# MOTOR.net
KiCad netlist of a schematic drawn in Altium Designer
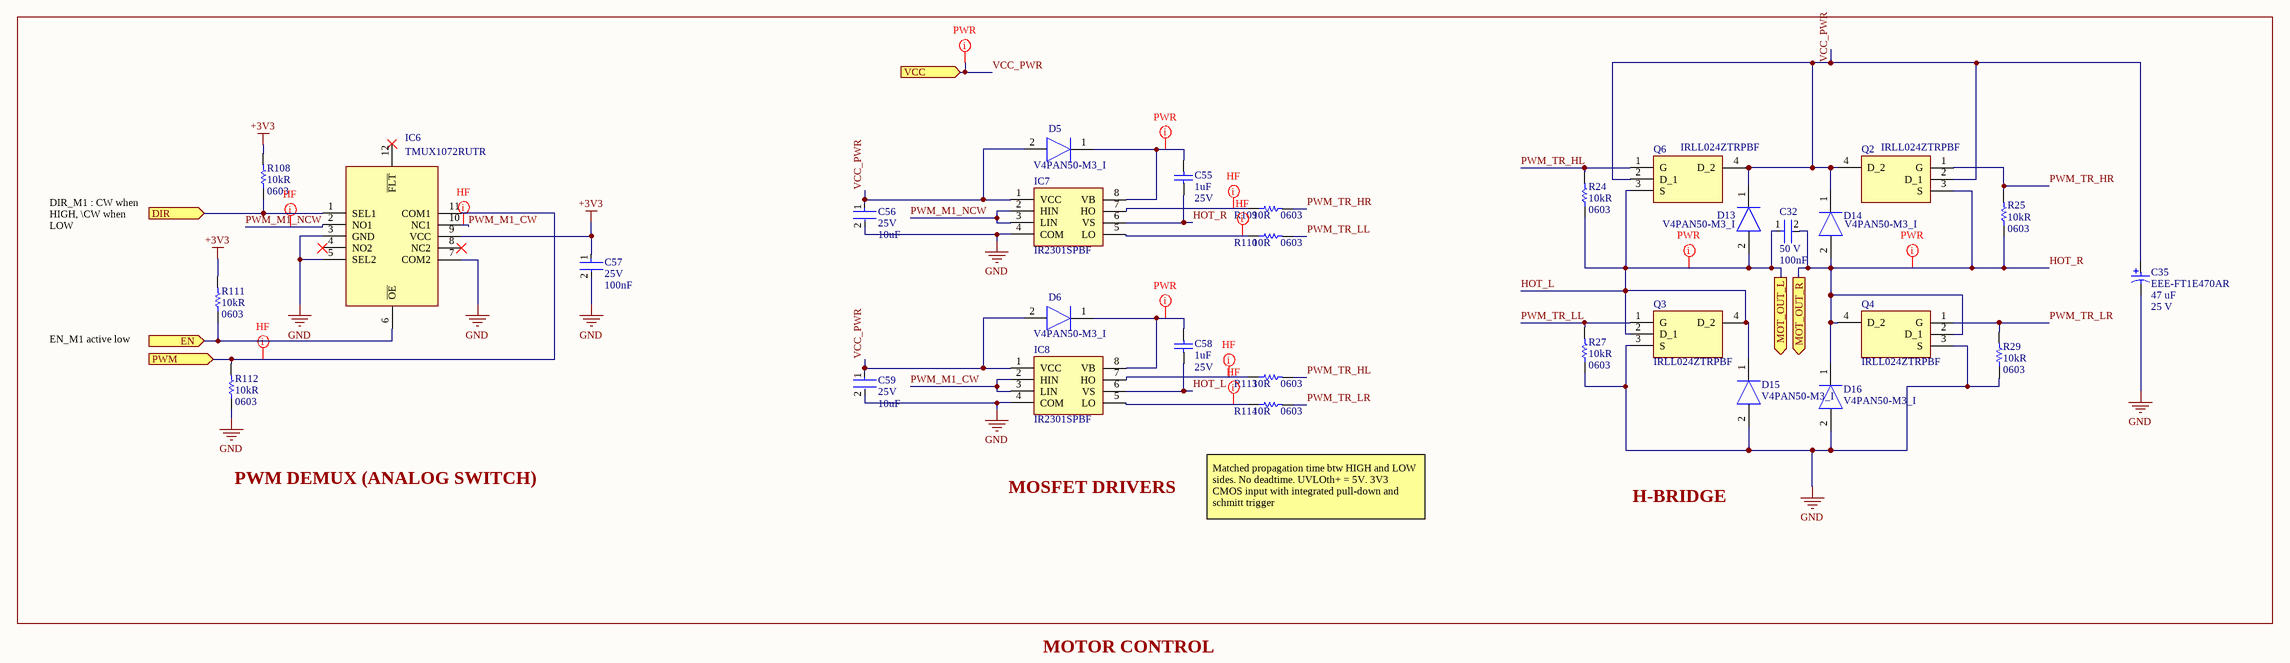
[diagram p0: MOTOR.SchDoc]

(export (version "E")
  (design (tool "Eeschema 10.0.6"))
  (components
    (comp (ref "C32")
      (value "100nF")
      (footprint "FP-C0805C-DN-MFG")
      (description "CAP CER 0.1UF 50V X7R 0805")
      (fields
        (field (name "MANUFACTURER PART NUMBER") "C0805C104K5RACTU")
        (field (name "VOLTAGE RATING") "50 V")
        (field (name "MANUFACTURER") "KEMET")
      )
      (libsource (lib "Altium Content Vault") (part "b4654b650e69147ec39a6b967a45e02"))
    )
    (comp (ref "C35")
      (value "EEE-FT1E470AR")
      (footprint "PNSC-FT-V-53x53-2_V")
      (fields
        (field (name "CAP.") "47 uF")
        (field (name "MANUFACTURER") "Panasonic")
        (field (name "RATED VOLTAGE") "25 V")
      )
      (libsource (lib "Altium Content Vault") (part "PNSC-CAP-P-2"))
    )
    (comp (ref "C55")
      (value "C0603C105K3PAC7867")
      (footprint "CAPC1608X90X35LL15T15")
      (fields
        (field (name "MANUFACTURER") "Kemet")
        (field (name "MANUFACTURER PART NUMBER") "C0603C105K3PACTU")
        (field (name "CAPACITANCE") "1uF")
        (field (name "TOLERANCE") "10%")
        (field (name "VOLTAGE RATING (DC)") "25V")
      )
      (libsource (lib "Altium Content Vault") (part "CAP"))
    )
    (comp (ref "C56")
      (value "C2012X5R1E106K125AB")
      (footprint "FP-C2012-125-0_2-IPC_B")
      (description "Multilayer Ceramic Capacitors 10μF ±10% 25V X5R SMD 0805")
      (fields
        (field (name "VOLTAGE") "25V")
        (field (name "VOLTAGE RATING (DC)") "25V")
        (field (name "TOLERANCE") "10%")
        (field (name "CAPACITANCE") "10uF")
      )
      (libsource (lib "Altium Content Vault") (part "b4654b650e69147ec39a6b967a45e02"))
    )
    (comp (ref "C57")
      (value "CGA3E2X7R1E104K080AA")
      (footprint "FP-CGA3E-0_3-0_1-MFG")
      (description "Cap Ceramic 100nF 25V X7R 10% Pad SMD 0603 +125°C Automotive T/R")
      (fields
        (field (name "VOLTAGE RATING (DC)") "25V")
        (field (name "CAPACITANCE") "100nF")
        (field (name "TOLERANCE") "10%")
        (field (name "MANUFACTURER") "TDK")
      )
      (libsource (lib "Altium Content Vault") (part "b4654b650e69147ec39a6b967a45e02"))
    )
    (comp (ref "C58")
      (value "C0603C105K3PAC7867")
      (footprint "CAPC1608X90X35LL15T15")
      (fields
        (field (name "MANUFACTURER") "Kemet")
        (field (name "MANUFACTURER PART NUMBER") "C0603C105K3PACTU")
        (field (name "CAPACITANCE") "1uF")
        (field (name "TOLERANCE") "10%")
        (field (name "VOLTAGE RATING (DC)") "25V")
      )
      (libsource (lib "Altium Content Vault") (part "CAP"))
    )
    (comp (ref "C59")
      (value "C2012X5R1E106K125AB")
      (footprint "FP-C2012-125-0_2-IPC_B")
      (description "Multilayer Ceramic Capacitors 10μF ±10% 25V X5R SMD 0805")
      (fields
        (field (name "VOLTAGE") "25V")
        (field (name "VOLTAGE RATING (DC)") "25V")
        (field (name "TOLERANCE") "10%")
        (field (name "CAPACITANCE") "10uF")
      )
      (libsource (lib "Altium Content Vault") (part "b4654b650e69147ec39a6b967a45e02"))
    )
    (comp (ref "D5")
      (value "V4PAN50-M3_I")
      (footprint "SamacSys:V4PAN50M3I")
      (description "Diode")
      (fields
        (field (name "MANUFACTURER_PART_NUMBER") "V4PAN50-M3/I")
        (field (name "MOUSER PART NUMBER") "78-V4PAN50-M3/I")
      )
      (libsource (lib "*") (part "V4PAN50-M3_I"))
    )
    (comp (ref "D6")
      (value "V4PAN50-M3_I")
      (footprint "SamacSys:V4PAN50M3I")
      (description "Diode")
      (fields
        (field (name "MANUFACTURER_PART_NUMBER") "V4PAN50-M3/I")
        (field (name "MOUSER PART NUMBER") "78-V4PAN50-M3/I")
      )
      (libsource (lib "*") (part "V4PAN50-M3_I"))
    )
    (comp (ref "D13")
      (value "V4PAN50-M3_I")
      (footprint "SamacSys:V4PAN50M3I")
      (description "Diode")
      (fields
        (field (name "MANUFACTURER_PART_NUMBER") "V4PAN50-M3/I")
        (field (name "MOUSER PART NUMBER") "78-V4PAN50-M3/I")
      )
      (libsource (lib "*") (part "V4PAN50-M3_I"))
    )
    (comp (ref "D14")
      (value "V4PAN50-M3_I")
      (footprint "SamacSys:V4PAN50M3I")
      (description "Diode")
      (fields
        (field (name "MANUFACTURER_PART_NUMBER") "V4PAN50-M3/I")
        (field (name "MOUSER PART NUMBER") "78-V4PAN50-M3/I")
      )
      (libsource (lib "*") (part "V4PAN50-M3_I"))
    )
    (comp (ref "D15")
      (value "V4PAN50-M3_I")
      (footprint "SamacSys:V4PAN50M3I")
      (description "Diode")
      (fields
        (field (name "MANUFACTURER_PART_NUMBER") "V4PAN50-M3/I")
        (field (name "MOUSER PART NUMBER") "78-V4PAN50-M3/I")
      )
      (libsource (lib "*") (part "V4PAN50-M3_I"))
    )
    (comp (ref "D16")
      (value "V4PAN50-M3_I")
      (footprint "SamacSys:V4PAN50M3I")
      (description "Diode")
      (fields
        (field (name "MANUFACTURER_PART_NUMBER") "V4PAN50-M3/I")
        (field (name "MOUSER PART NUMBER") "78-V4PAN50-M3/I")
      )
      (libsource (lib "*") (part "V4PAN50-M3_I"))
    )
    (comp (ref "IC6")
      (value "TMUX1072RUTR")
      (footprint "SamacSys:QFN40P170X200X55-12N")
      (description "Integrated Circuit")
      (fields (field (name "MOUSER PART NUMBER") "595-TMUX1072RUTR"))
      (libsource (lib "*") (part "TMUX1072RUTR"))
    )
    (comp (ref "IC7")
      (value "IR2301SPBF")
      (footprint "SamacSys:SOIC127P600X175-8N")
      (description "Integrated Circuit")
      (fields (field (name "MOUSER PART NUMBER") "942-IR2301SPBF"))
      (libsource (lib "*") (part "IR2301SPBF"))
    )
    (comp (ref "IC8")
      (value "IR2301SPBF")
      (footprint "SamacSys:SOIC127P600X175-8N")
      (description "Integrated Circuit")
      (fields (field (name "MOUSER PART NUMBER") "942-IR2301SPBF"))
      (libsource (lib "*") (part "IR2301SPBF"))
    )
    (comp (ref "Q2")
      (value "IRLL024ZTRPBF")
      (footprint "SamacSys:SOT230P700X180-4N")
      (description "MOSFET (N-Channel)")
      (fields
        (field (name "MANUFACTURER_PART_NUMBER") "IRLL2705TRPBF")
        (field (name "MOUSER PART NUMBER") "942-IRLL2705TRPBF")
      )
      (libsource (lib "") (part "IRLL2705TRPBF_1"))
    )
    (comp (ref "Q3")
      (value "IRLL024ZTRPBF")
      (footprint "SamacSys:SOT230P700X180-4N")
      (description "MOSFET (N-Channel)")
      (fields
        (field (name "MANUFACTURER_PART_NUMBER") "IRLL2705TRPBF")
        (field (name "MOUSER PART NUMBER") "942-IRLL2705TRPBF")
      )
      (libsource (lib "*") (part "IRLL2705TRPBF"))
    )
    (comp (ref "Q4")
      (value "IRLL024ZTRPBF")
      (footprint "SamacSys:SOT230P700X180-4N")
      (description "MOSFET (N-Channel)")
      (fields
        (field (name "MANUFACTURER_PART_NUMBER") "IRLL2705TRPBF")
        (field (name "MOUSER PART NUMBER") "942-IRLL2705TRPBF")
      )
      (libsource (lib "") (part "IRLL2705TRPBF_1"))
    )
    (comp (ref "Q6")
      (value "IRLL024ZTRPBF")
      (footprint "SamacSys:SOT230P700X180-4N")
      (description "MOSFET (N-Channel)")
      (fields
        (field (name "MANUFACTURER_PART_NUMBER") "IRLL2705TRPBF")
        (field (name "MOUSER PART NUMBER") "942-IRLL2705TRPBF")
      )
      (libsource (lib "*") (part "IRLL2705TRPBF"))
    )
    (comp (ref "R24")
      (value "ERJ3EKF1002V")
      (footprint "RESC1609X55X30LL15T15")
      (description "Chip Resistor, 10 KOhm, +/- 1%, 0.1 W, -55 to 155 degC, 0603 (1608 Metric), RoHS, Tape and Reel")
      (fields
        (field (name "RESISTANCE") "10kR")
        (field (name "CASE CODE (IMPERIAL)") "0603")
        (field (name "TOLERANCE") "1%")
        (field (name "MANUFACTURER") "Panasonic")
      )
      (libsource (lib "Altium Content Vault") (part "RES-2"))
    )
    (comp (ref "R25")
      (value "ERJ3EKF1002V")
      (footprint "RESC1609X55X30LL15T15")
      (description "Chip Resistor, 10 KOhm, +/- 1%, 0.1 W, -55 to 155 degC, 0603 (1608 Metric), RoHS, Tape and Reel")
      (fields
        (field (name "RESISTANCE") "10kR")
        (field (name "CASE CODE (IMPERIAL)") "0603")
        (field (name "TOLERANCE") "1%")
        (field (name "MANUFACTURER") "Panasonic")
      )
      (libsource (lib "Altium Content Vault") (part "RES-2"))
    )
    (comp (ref "R27")
      (value "ERJ3EKF1002V")
      (footprint "RESC1609X55X30LL15T15")
      (description "Chip Resistor, 10 KOhm, +/- 1%, 0.1 W, -55 to 155 degC, 0603 (1608 Metric), RoHS, Tape and Reel")
      (fields
        (field (name "RESISTANCE") "10kR")
        (field (name "CASE CODE (IMPERIAL)") "0603")
        (field (name "TOLERANCE") "1%")
        (field (name "MANUFACTURER") "Panasonic")
      )
      (libsource (lib "Altium Content Vault") (part "RES-2"))
    )
    (comp (ref "R29")
      (value "ERJ3EKF1002V")
      (footprint "RESC1609X55X30LL15T15")
      (description "Chip Resistor, 10 KOhm, +/- 1%, 0.1 W, -55 to 155 degC, 0603 (1608 Metric), RoHS, Tape and Reel")
      (fields
        (field (name "RESISTANCE") "10kR")
        (field (name "CASE CODE (IMPERIAL)") "0603")
        (field (name "TOLERANCE") "1%")
        (field (name "MANUFACTURER") "Panasonic")
      )
      (libsource (lib "Altium Content Vault") (part "RES-2"))
    )
    (comp (ref "R108")
      (value "ERJ3EKF1002V")
      (footprint "RESC1609X55X30LL15T15")
      (description "Chip Resistor, 10 KOhm, +/- 1%, 0.1 W, -55 to 155 degC, 0603 (1608 Metric), RoHS, Tape and Reel")
      (fields
        (field (name "RESISTANCE") "10kR")
        (field (name "CASE CODE (IMPERIAL)") "0603")
        (field (name "TOLERANCE") "1%")
        (field (name "MANUFACTURER") "Panasonic")
      )
      (libsource (lib "Altium Content Vault") (part "RES-2"))
    )
    (comp (ref "R109")
      (value "RC0603FR-0710RL")
      (footprint "RESC1608X55X25NL10T15")
      (description "Chip Resistor, 10 Ohm, +/- 1%, 0.1 W, -55 to 155 degC, 0603 (1608 Metric), RoHS, Tape and Reel")
      (fields
        (field (name "MANUFACTURER") "Yageo")
        (field (name "CASE/PACKAGE") "0603")
        (field (name "RESISTANCE") "10R")
        (field (name "TOLERANCE") "1%")
      )
      (libsource (lib "Altium Content Vault") (part "RES-2"))
    )
    (comp (ref "R110")
      (value "RC0603FR-0710RL")
      (footprint "RESC1608X55X25NL10T15")
      (description "Chip Resistor, 10 Ohm, +/- 1%, 0.1 W, -55 to 155 degC, 0603 (1608 Metric), RoHS, Tape and Reel")
      (fields
        (field (name "MANUFACTURER") "Yageo")
        (field (name "CASE/PACKAGE") "0603")
        (field (name "RESISTANCE") "10R")
        (field (name "TOLERANCE") "1%")
      )
      (libsource (lib "Altium Content Vault") (part "RES-2"))
    )
    (comp (ref "R111")
      (value "ERJ3EKF1002V")
      (footprint "RESC1609X55X30LL15T15")
      (description "Chip Resistor, 10 KOhm, +/- 1%, 0.1 W, -55 to 155 degC, 0603 (1608 Metric), RoHS, Tape and Reel")
      (fields
        (field (name "RESISTANCE") "10kR")
        (field (name "CASE CODE (IMPERIAL)") "0603")
        (field (name "TOLERANCE") "1%")
        (field (name "MANUFACTURER") "Panasonic")
      )
      (libsource (lib "Altium Content Vault") (part "RES-2"))
    )
    (comp (ref "R112")
      (value "ERJ3EKF1002V")
      (footprint "RESC1609X55X30LL15T15")
      (description "Chip Resistor, 10 KOhm, +/- 1%, 0.1 W, -55 to 155 degC, 0603 (1608 Metric), RoHS, Tape and Reel")
      (fields
        (field (name "RESISTANCE") "10kR")
        (field (name "CASE CODE (IMPERIAL)") "0603")
        (field (name "TOLERANCE") "1%")
        (field (name "MANUFACTURER") "Panasonic")
      )
      (libsource (lib "Altium Content Vault") (part "RES-2"))
    )
    (comp (ref "R113")
      (value "RC0603FR-0710RL")
      (footprint "RESC1608X55X25NL10T15")
      (description "Chip Resistor, 10 Ohm, +/- 1%, 0.1 W, -55 to 155 degC, 0603 (1608 Metric), RoHS, Tape and Reel")
      (fields
        (field (name "MANUFACTURER") "Yageo")
        (field (name "CASE/PACKAGE") "0603")
        (field (name "RESISTANCE") "10R")
        (field (name "TOLERANCE") "1%")
      )
      (libsource (lib "Altium Content Vault") (part "RES-2"))
    )
    (comp (ref "R114")
      (value "RC0603FR-0710RL")
      (footprint "RESC1608X55X25NL10T15")
      (description "Chip Resistor, 10 Ohm, +/- 1%, 0.1 W, -55 to 155 degC, 0603 (1608 Metric), RoHS, Tape and Reel")
      (fields
        (field (name "MANUFACTURER") "Yageo")
        (field (name "CASE/PACKAGE") "0603")
        (field (name "RESISTANCE") "10R")
        (field (name "TOLERANCE") "1%")
      )
      (libsource (lib "Altium Content Vault") (part "RES-2"))
    )
  )
  (nets
    (net (code "1") (name "+3V3") (class "Default")
      (node (ref "C57") (pin "1") (pinfunction "1_1") (pintype "passive"))
      (node (ref "IC6") (pin "9") (pinfunction "VCC_9") (pintype "passive"))
      (node (ref "R108") (pin "2") (pinfunction "2_2") (pintype "passive"))
      (node (ref "R111") (pin "2") (pinfunction "2_2") (pintype "passive"))
    )
    (net (code "2") (name "/DIR") (class "Default")
      (node (ref "IC6") (pin "1") (pinfunction "SEL1_1") (pintype "passive"))
      (node (ref "R108") (pin "1") (pinfunction "1_1") (pintype "passive"))
    )
    (net (code "3") (name "/EN") (class "Default")
      (node (ref "IC6") (pin "6") (pinfunction "~{OE}_6") (pintype "passive"))
      (node (ref "R111") (pin "1") (pinfunction "1_1") (pintype "passive"))
    )
    (net (code "4") (name "/HOT_L") (class "Default")
      (node (ref "C32") (pin "1") (pinfunction "1_1") (pintype "passive"))
      (node (ref "C58") (pin "1") (pinfunction "1_1") (pintype "passive"))
      (node (ref "D13") (pin "2") (pinfunction "A_2") (pintype "passive"))
      (node (ref "D15") (pin "1") (pinfunction "K_1") (pintype "passive"))
      (node (ref "IC8") (pin "6") (pinfunction "VS_6") (pintype "passive"))
      (node (ref "Q3") (pin "2") (pinfunction "D_1_2") (pintype "passive"))
      (node (ref "Q3") (pin "4") (pinfunction "D_2_4") (pintype "passive"))
      (node (ref "Q6") (pin "3") (pinfunction "S_3") (pintype "passive"))
      (node (ref "R24") (pin "1") (pinfunction "1_1") (pintype "passive"))
    )
    (net (code "5") (name "/HOT_R") (class "Default")
      (node (ref "C32") (pin "2") (pinfunction "2_2") (pintype "passive"))
      (node (ref "C55") (pin "1") (pinfunction "1_1") (pintype "passive"))
      (node (ref "D14") (pin "2") (pinfunction "A_2") (pintype "passive"))
      (node (ref "D16") (pin "1") (pinfunction "K_1") (pintype "passive"))
      (node (ref "IC7") (pin "6") (pinfunction "VS_6") (pintype "passive"))
      (node (ref "Q2") (pin "3") (pinfunction "S_3") (pintype "passive"))
      (node (ref "Q4") (pin "2") (pinfunction "D_1_2") (pintype "passive"))
      (node (ref "Q4") (pin "4") (pinfunction "D_2_4") (pintype "passive"))
      (node (ref "R25") (pin "1") (pinfunction "1_1") (pintype "passive"))
    )
    (net (code "6") (name "/PWM") (class "Default")
      (node (ref "IC6") (pin "11") (pinfunction "COM1_11") (pintype "passive"))
      (node (ref "R112") (pin "2") (pinfunction "2_2") (pintype "passive"))
    )
    (net (code "7") (name "/PWM_M1_CW") (class "Default")
      (node (ref "IC6") (pin "10") (pinfunction "NC1_10") (pintype "passive"))
      (node (ref "IC8") (pin "2") (pinfunction "HIN_2") (pintype "passive"))
      (node (ref "IC8") (pin "3") (pinfunction "LIN_3") (pintype "passive"))
    )
    (net (code "8") (name "/PWM_M1_NCW") (class "Default")
      (node (ref "IC6") (pin "2") (pinfunction "NO1_2") (pintype "passive"))
      (node (ref "IC7") (pin "2") (pinfunction "HIN_2") (pintype "passive"))
      (node (ref "IC7") (pin "3") (pinfunction "LIN_3") (pintype "passive"))
    )
    (net (code "9") (name "/PWM_TR_HL") (class "Default")
      (node (ref "Q6") (pin "1") (pinfunction "G_1") (pintype "passive"))
      (node (ref "R113") (pin "2") (pinfunction "2_2") (pintype "passive"))
      (node (ref "R24") (pin "2") (pinfunction "2_2") (pintype "passive"))
    )
    (net (code "10") (name "/PWM_TR_HR") (class "Default")
      (node (ref "Q2") (pin "1") (pinfunction "G_1") (pintype "passive"))
      (node (ref "R109") (pin "2") (pinfunction "2_2") (pintype "passive"))
      (node (ref "R25") (pin "2") (pinfunction "2_2") (pintype "passive"))
    )
    (net (code "11") (name "/PWM_TR_LL") (class "Default")
      (node (ref "Q3") (pin "1") (pinfunction "G_1") (pintype "passive"))
      (node (ref "R110") (pin "2") (pinfunction "2_2") (pintype "passive"))
      (node (ref "R27") (pin "2") (pinfunction "2_2") (pintype "passive"))
    )
    (net (code "12") (name "/PWM_TR_LR") (class "Default")
      (node (ref "Q4") (pin "1") (pinfunction "G_1") (pintype "passive"))
      (node (ref "R114") (pin "2") (pinfunction "2_2") (pintype "passive"))
      (node (ref "R29") (pin "2") (pinfunction "2_2") (pintype "passive"))
    )
    (net (code "13") (name "/VCC_PWR") (class "Default")
      (node (ref "C35") (pin "1") (pinfunction "1_1") (pintype "passive"))
      (node (ref "C56") (pin "1") (pinfunction "1_1") (pintype "passive"))
      (node (ref "C59") (pin "1") (pinfunction "1_1") (pintype "passive"))
      (node (ref "D13") (pin "1") (pinfunction "K_1") (pintype "passive"))
      (node (ref "D14") (pin "1") (pinfunction "K_1") (pintype "passive"))
      (node (ref "D5") (pin "2") (pinfunction "A_2") (pintype "passive"))
      (node (ref "D6") (pin "2") (pinfunction "A_2") (pintype "passive"))
      (node (ref "IC7") (pin "1") (pinfunction "VCC_1") (pintype "passive"))
      (node (ref "IC8") (pin "1") (pinfunction "VCC_1") (pintype "passive"))
      (node (ref "Q2") (pin "2") (pinfunction "D_1_2") (pintype "passive"))
      (node (ref "Q2") (pin "4") (pinfunction "D_2_4") (pintype "passive"))
      (node (ref "Q6") (pin "2") (pinfunction "D_1_2") (pintype "passive"))
      (node (ref "Q6") (pin "4") (pinfunction "D_2_4") (pintype "passive"))
    )
    (net (code "14") (name "GND") (class "Default")
      (node (ref "C35") (pin "2") (pinfunction "2_2") (pintype "passive"))
      (node (ref "C56") (pin "2") (pinfunction "2_2") (pintype "passive"))
      (node (ref "C57") (pin "2") (pinfunction "2_2") (pintype "passive"))
      (node (ref "C59") (pin "2") (pinfunction "2_2") (pintype "passive"))
      (node (ref "D15") (pin "2") (pinfunction "A_2") (pintype "passive"))
      (node (ref "D16") (pin "2") (pinfunction "A_2") (pintype "passive"))
      (node (ref "IC6") (pin "3") (pinfunction "GND_3") (pintype "passive"))
      (node (ref "IC6") (pin "5") (pinfunction "SEL2_5") (pintype "passive"))
      (node (ref "IC6") (pin "7") (pinfunction "COM2_7") (pintype "passive"))
      (node (ref "IC7") (pin "4") (pinfunction "COM_4") (pintype "passive"))
      (node (ref "IC8") (pin "4") (pinfunction "COM_4") (pintype "passive"))
      (node (ref "Q3") (pin "3") (pinfunction "S_3") (pintype "passive"))
      (node (ref "Q4") (pin "3") (pinfunction "S_3") (pintype "passive"))
      (node (ref "R112") (pin "1") (pinfunction "1_1") (pintype "passive"))
      (node (ref "R27") (pin "1") (pinfunction "1_1") (pintype "passive"))
      (node (ref "R29") (pin "1") (pinfunction "1_1") (pintype "passive"))
    )
    (net (code "15") (name "Net-(D5-K)") (class "Default")
      (node (ref "C55") (pin "2") (pinfunction "2_2") (pintype "passive"))
      (node (ref "D5") (pin "1") (pinfunction "K_1") (pintype "passive"))
      (node (ref "IC7") (pin "8") (pinfunction "VB_8") (pintype "passive"))
    )
    (net (code "16") (name "Net-(D6-K)") (class "Default")
      (node (ref "C58") (pin "2") (pinfunction "2_2") (pintype "passive"))
      (node (ref "D6") (pin "1") (pinfunction "K_1") (pintype "passive"))
      (node (ref "IC8") (pin "8") (pinfunction "VB_8") (pintype "passive"))
    )
    (net (code "17") (name "Net-(IC7-HO)") (class "Default")
      (node (ref "IC7") (pin "7") (pinfunction "HO_7") (pintype "passive"))
      (node (ref "R109") (pin "1") (pinfunction "1_1") (pintype "passive"))
    )
    (net (code "18") (name "Net-(IC7-LO)") (class "Default")
      (node (ref "IC7") (pin "5") (pinfunction "LO_5") (pintype "passive"))
      (node (ref "R110") (pin "1") (pinfunction "1_1") (pintype "passive"))
    )
    (net (code "19") (name "Net-(IC8-HO)") (class "Default")
      (node (ref "IC8") (pin "7") (pinfunction "HO_7") (pintype "passive"))
      (node (ref "R113") (pin "1") (pinfunction "1_1") (pintype "passive"))
    )
    (net (code "20") (name "Net-(IC8-LO)") (class "Default")
      (node (ref "IC8") (pin "5") (pinfunction "LO_5") (pintype "passive"))
      (node (ref "R114") (pin "1") (pinfunction "1_1") (pintype "passive"))
    )
    (net (code "21") (name "unconnected-(IC6-NC2-Pad8)") (class "Default")
      (node (ref "IC6") (pin "8") (pinfunction "NC2_8") (pintype "passive+no_connect"))
    )
    (net (code "22") (name "unconnected-(IC6-NO2-Pad4)") (class "Default")
      (node (ref "IC6") (pin "4") (pinfunction "NO2_4") (pintype "passive+no_connect"))
    )
    (net (code "23") (name "unconnected-(IC6-~{FLT}-Pad12)") (class "Default")
      (node (ref "IC6") (pin "12") (pinfunction "~{FLT}_12") (pintype "passive+no_connect"))
    )
  )
)
